# light_switch_hi_volt.net
KiCad netlist of a schematic drawn in EAGLE
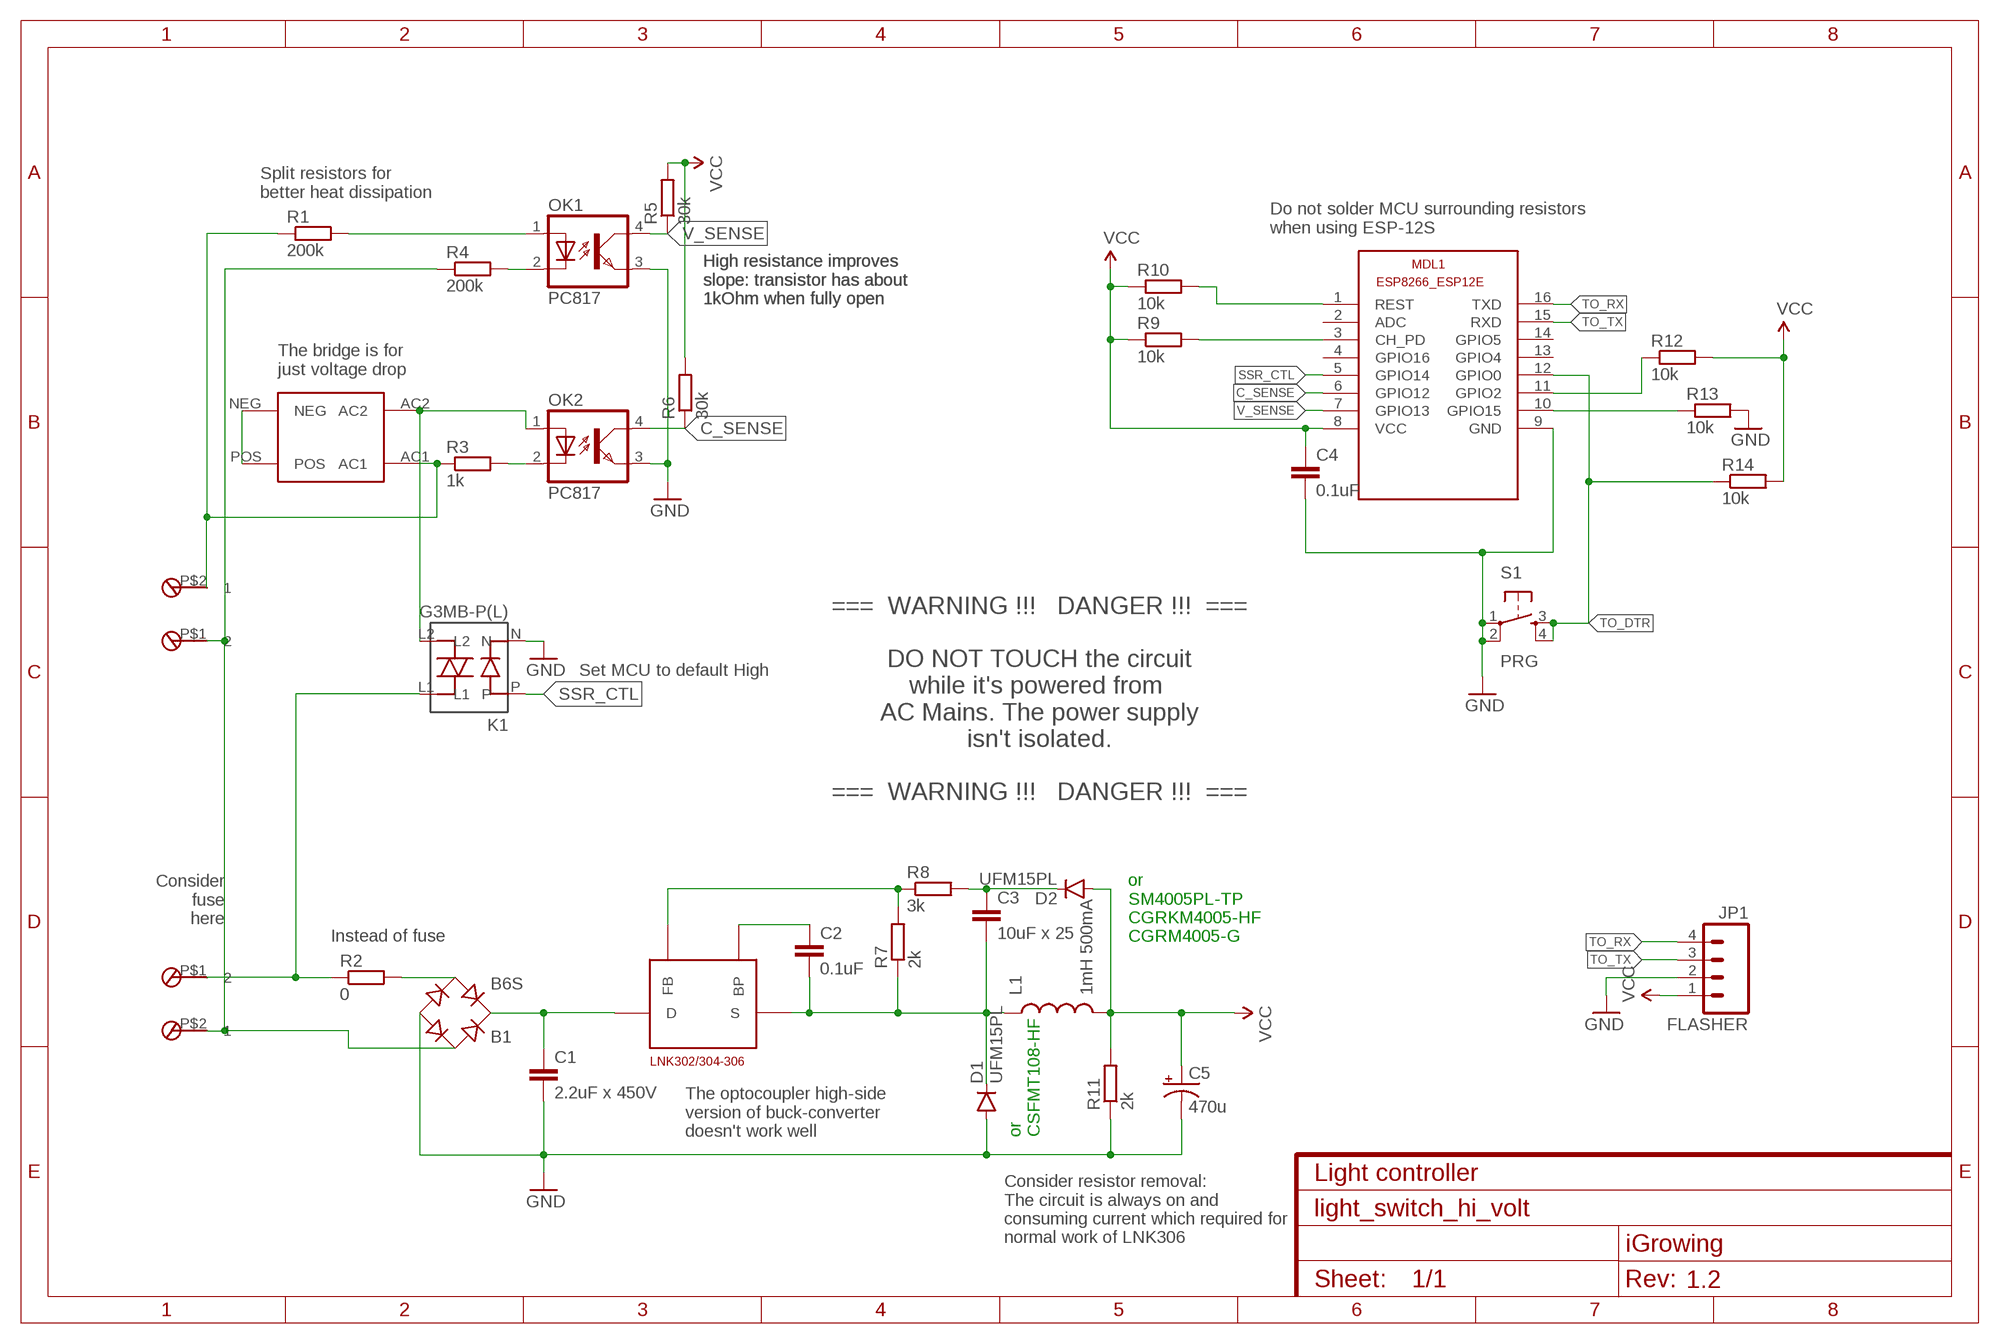
[diagram p0: schematic, sheet 1]

(export (version "E")
  (design (tool "Eeschema 10.0.6"))
  (components
    (comp (ref "B1")
      (value "B6S")
      (footprint "eagle-import:MBS")
      (libsource (lib "eagle-import") (part "BS6"))
    )
    (comp (ref "C1")
      (value "2.2uF x 450V")
      (footprint "eagle-import:C2220K")
      (fields (field (name "MPN") "CKG57NX7T2W225M500JH"))
      (libsource (lib "eagle-import") (part "C-EUC2220K"))
    )
    (comp (ref "C2")
      (value "0.1uF")
      (footprint "eagle-import:0805")
      (fields (field (name "MF") "Taiyo Yuden (U.S.A.), Inc.") (field (name "MPN") "TMK107BJ104KA-T"))
      (libsource (lib "eagle-import") (part "CAP0805"))
    )
    (comp (ref "C3")
      (value "10uF x 25")
      (footprint "eagle-import:0805")
      (fields (field (name "MPN") "GRM219R61E106KA12D"))
      (libsource (lib "eagle-import") (part "SparkFun-Passives_CAP0805"))
    )
    (comp (ref "C4")
      (value "0.1uF")
      (footprint "eagle-import:0805")
      (fields (field (name "MF") "Taiyo Yuden (U.S.A.), Inc.") (field (name "MPN") "TMK107BJ104KA-T"))
      (libsource (lib "eagle-import") (part "CAP0805"))
    )
    (comp (ref "C5")
      (value "470u")
      (footprint "eagle-import:EIA7343")
      (libsource (lib "eagle-import") (part "CAP_POL7343"))
    )
    (comp (ref "D1")
      (value "UFM15PL")
      (footprint "eagle-import:SOD-123")
      (fields (field (name "MPN") "UFM15PL-TP"))
      (libsource (lib "eagle-import") (part "DIODESOD123"))
    )
    (comp (ref "D2")
      (value "UFM15PL")
      (footprint "eagle-import:SOD-123")
      (fields (field (name "MPN") "UFM15PL-TP"))
      (libsource (lib "eagle-import") (part "DIODESOD123"))
    )
    (comp (ref "J1")
      (value "2POS_TERM_BLK_10A_3.5MM")
      (footprint "eagle-import:2POS_TERM_BLK_10A_3.5MM")
      (libsource (lib "eagle-import") (part "2POS_TERM_BLK_10A_3.5MM"))
    )
    (comp (ref "J2")
      (value "2POS_TERM_BLK_10A_3.5MM")
      (footprint "eagle-import:2POS_TERM_BLK_10A_3.5MM")
      (libsource (lib "eagle-import") (part "2POS_TERM_BLK_10A_3.5MM"))
    )
    (comp (ref "JP1")
      (value "FLASHER")
      (footprint "eagle-import:1X04")
      (libsource (lib "eagle-import") (part "M04PTH"))
    )
    (comp (ref "K1")
      (value "G3MB-P(L)")
      (footprint "eagle-import:GB3M_SSR")
      (libsource (lib "eagle-import") (part "G3MB"))
    )
    (comp (ref "L1")
      (value "1mH 500mA")
      (footprint "eagle-import:CDRH125")
      (fields (field (name "MPN") "46105C"))
      (libsource (lib "eagle-import") (part "INDUCTORPWR"))
    )
    (comp (ref "MDL1")
      (value "ESP8266-12EESP8266-ESP12E")
      (footprint "eagle-import:ESP8266-ESP12E")
      (libsource (lib "eagle-import") (part "ESP8266-12EESP8266-ESP12E"))
    )
    (comp (ref "OK1")
      (value "PC817")
      (footprint "eagle-import:SMD4")
      (libsource (lib "eagle-import") (part "LTV816S"))
    )
    (comp (ref "OK2")
      (value "PC817")
      (footprint "eagle-import:SMD4")
      (libsource (lib "eagle-import") (part "LTV816S"))
    )
    (comp (ref "R1")
      (value "200k")
      (footprint "eagle-import:R0805")
      (fields (field (name "MF") "VISHAY/DALE") (field (name "MPN") "CRCW06032K00FKEA"))
      (libsource (lib "eagle-import") (part "resistor_R-EU_R0805"))
    )
    (comp (ref "R2")
      (value "0")
      (footprint "eagle-import:R0603")
      (fields (field (name "MF") "VISHAY/DALE") (field (name "MPN") "CRCW06032K00FKEA"))
      (libsource (lib "eagle-import") (part "resistor_R-EU_R0603"))
    )
    (comp (ref "R3")
      (value "1k")
      (footprint "eagle-import:R0603")
      (fields (field (name "MF") "VISHAY/DALE") (field (name "MPN") "CRCW06032K00FKEA"))
      (libsource (lib "eagle-import") (part "resistor_R-EU_R0603"))
    )
    (comp (ref "R4")
      (value "200k")
      (footprint "eagle-import:R0805")
      (fields (field (name "MF") "VISHAY/DALE") (field (name "MPN") "CRCW06032K00FKEA"))
      (libsource (lib "eagle-import") (part "resistor_R-EU_R0805"))
    )
    (comp (ref "R5")
      (value "30k")
      (footprint "eagle-import:R0603")
      (fields (field (name "MF") "VISHAY/DALE") (field (name "MPN") "CRCW06032K00FKEA"))
      (libsource (lib "eagle-import") (part "resistor_R-EU_R0603"))
    )
    (comp (ref "R6")
      (value "30k")
      (footprint "eagle-import:R0603")
      (fields (field (name "MF") "VISHAY/DALE") (field (name "MPN") "CRCW06032K00FKEA"))
      (libsource (lib "eagle-import") (part "resistor_R-EU_R0603"))
    )
    (comp (ref "R7")
      (value "2k")
      (footprint "eagle-import:R0603")
      (fields (field (name "MF") "VISHAY/DALE") (field (name "MPN") "CRCW06032K00FKEA"))
      (libsource (lib "eagle-import") (part "resistor_R-EU_R0603"))
    )
    (comp (ref "R8")
      (value "3k")
      (footprint "eagle-import:R0603")
      (fields (field (name "MF") "VISHAY/DALE") (field (name "MPN") "CRCW06032K00FKEA"))
      (libsource (lib "eagle-import") (part "resistor_R-EU_R0603"))
    )
    (comp (ref "R9")
      (value "10k")
      (footprint "eagle-import:R0603")
      (libsource (lib "eagle-import") (part "R-EU_R0603"))
    )
    (comp (ref "R10")
      (value "10k")
      (footprint "eagle-import:R0603")
      (libsource (lib "eagle-import") (part "R-EU_R0603"))
    )
    (comp (ref "R11")
      (value "2k")
      (footprint "eagle-import:R0603")
      (fields (field (name "MF") "VISHAY/DALE") (field (name "MPN") "CRCW06032K00FKEA"))
      (libsource (lib "eagle-import") (part "resistor_R-EU_R0603"))
    )
    (comp (ref "R12")
      (value "10k")
      (footprint "eagle-import:R0603")
      (libsource (lib "eagle-import") (part "R-EU_R0603"))
    )
    (comp (ref "R13")
      (value "10k")
      (footprint "eagle-import:R0603")
      (libsource (lib "eagle-import") (part "R-EU_R0603"))
    )
    (comp (ref "R14")
      (value "10k")
      (footprint "eagle-import:R0603")
      (libsource (lib "eagle-import") (part "R-EU_R0603"))
    )
    (comp (ref "S1")
      (value "PRG")
      (footprint "eagle-import:TACTILE-SWITCH-SMD")
      (libsource (lib "eagle-import") (part "TAC_SWITCHSMD"))
    )
    (comp (ref "U1")
      (value "Z4DGP406L-HF")
      (footprint "eagle-import:Z4DGP406L-HF")
      (libsource (lib "eagle-import") (part "Z4DGP406L-HF"))
    )
    (comp (ref "U2")
      (value "LNK306")
      (footprint "eagle-import:SO08")
      (fields (field (name "MPN") "LNK306GN"))
      (libsource (lib "eagle-import") (part "LNK306"))
    )
  )
  (nets
    (net (code "1") (name "C_SENSE") (class "Default")
      (node (ref "MDL1") (pin "6") (pinfunction "GPIO12_6") (pintype "bidirectional"))
      (node (ref "OK2") (pin "4") (pinfunction "COL_4") (pintype "passive"))
      (node (ref "R6") (pin "1") (pinfunction "1_1") (pintype "passive"))
    )
    (net (code "2") (name "GND") (class "Default")
      (node (ref "B1") (pin "-") (pinfunction "-_-") (pintype "passive"))
      (node (ref "C1") (pin "2") (pinfunction "2_2") (pintype "passive"))
      (node (ref "C4") (pin "2") (pinfunction "2_2") (pintype "passive"))
      (node (ref "C5") (pin "C") (pinfunction "-_C") (pintype "passive"))
      (node (ref "D1") (pin "A") (pinfunction "A_A") (pintype "passive"))
      (node (ref "JP1") (pin "2") (pinfunction "2_2") (pintype "passive"))
      (node (ref "K1") (pin "N") (pinfunction "N_N") (pintype "bidirectional"))
      (node (ref "MDL1") (pin "9") (pinfunction "GND_9") (pintype "bidirectional"))
      (node (ref "OK1") (pin "3") (pinfunction "EMIT_3") (pintype "passive"))
      (node (ref "OK2") (pin "3") (pinfunction "EMIT_3") (pintype "passive"))
      (node (ref "R11") (pin "1") (pinfunction "1_1") (pintype "passive"))
      (node (ref "R13") (pin "2") (pinfunction "2_2") (pintype "passive"))
      (node (ref "S1") (pin "1") (pinfunction "1_1") (pintype "passive"))
      (node (ref "S1") (pin "2") (pinfunction "2_2") (pintype "passive"))
    )
    (net (code "3") (name "Net-(B1-PadAC2)") (class "Default")
      (node (ref "B1") (pin "AC2") (pinfunction "AC2_AC2") (pintype "passive"))
      (node (ref "R2") (pin "2") (pinfunction "2_2") (pintype "passive"))
    )
    (net (code "4") (name "Net-(C2-Pad2)") (class "Default")
      (node (ref "C2") (pin "2") (pinfunction "2_2") (pintype "passive"))
      (node (ref "C3") (pin "2") (pinfunction "2_2") (pintype "passive"))
      (node (ref "D1") (pin "C") (pinfunction "C_C") (pintype "passive"))
      (node (ref "L1") (pin "1") (pinfunction "1_1") (pintype "passive"))
      (node (ref "R7") (pin "1") (pinfunction "1_1") (pintype "passive"))
      (node (ref "U2") (pin "5") (pinfunction "S_5") (pintype "bidirectional"))
      (node (ref "U2") (pin "6") (pinfunction "S_6") (pintype "bidirectional"))
      (node (ref "U2") (pin "7") (pinfunction "S_7") (pintype "bidirectional"))
      (node (ref "U2") (pin "8") (pinfunction "S_8") (pintype "bidirectional"))
    )
    (net (code "5") (name "Net-(C3-Pad1)") (class "Default")
      (node (ref "C3") (pin "1") (pinfunction "1_1") (pintype "passive"))
      (node (ref "D2") (pin "C") (pinfunction "C_C") (pintype "passive"))
      (node (ref "R8") (pin "2") (pinfunction "2_2") (pintype "passive"))
    )
    (net (code "6") (name "Net-(J1-1)") (class "Default")
      (node (ref "J1") (pin "P$2") (pinfunction "1_P$2") (pintype "bidirectional"))
      (node (ref "R1") (pin "1") (pinfunction "1_1") (pintype "passive"))
      (node (ref "R3") (pin "1") (pinfunction "1_1") (pintype "passive"))
      (node (ref "U1") (pin "AC1") (pinfunction "AC1_AC1") (pintype "input"))
    )
    (net (code "7") (name "Net-(J1-2)") (class "Default")
      (node (ref "B1") (pin "AC1") (pinfunction "AC1_AC1") (pintype "passive"))
      (node (ref "J1") (pin "P$1") (pinfunction "2_P$1") (pintype "bidirectional"))
      (node (ref "J2") (pin "P$2") (pinfunction "1_P$2") (pintype "bidirectional"))
      (node (ref "R4") (pin "1") (pinfunction "1_1") (pintype "passive"))
    )
    (net (code "8") (name "Net-(J2-2)") (class "Default")
      (node (ref "J2") (pin "P$1") (pinfunction "2_P$1") (pintype "bidirectional"))
      (node (ref "K1") (pin "L1") (pinfunction "L1_L1") (pintype "bidirectional"))
      (node (ref "R2") (pin "1") (pinfunction "1_1") (pintype "passive"))
    )
    (net (code "9") (name "Net-(MDL1-CH_PD)") (class "Default")
      (node (ref "MDL1") (pin "3") (pinfunction "CH_PD_3") (pintype "bidirectional"))
      (node (ref "R9") (pin "2") (pinfunction "2_2") (pintype "passive"))
    )
    (net (code "10") (name "Net-(MDL1-GPIO2)") (class "Default")
      (node (ref "MDL1") (pin "11") (pinfunction "GPIO2_11") (pintype "bidirectional"))
      (node (ref "R12") (pin "1") (pinfunction "1_1") (pintype "passive"))
    )
    (net (code "11") (name "Net-(MDL1-GPIO15)") (class "Default")
      (node (ref "MDL1") (pin "10") (pinfunction "GPIO15_10") (pintype "bidirectional"))
      (node (ref "R13") (pin "1") (pinfunction "1_1") (pintype "passive"))
    )
    (net (code "12") (name "Net-(MDL1-REST)") (class "Default")
      (node (ref "MDL1") (pin "1") (pinfunction "REST_1") (pintype "bidirectional"))
      (node (ref "R10") (pin "2") (pinfunction "2_2") (pintype "passive"))
    )
    (net (code "13") (name "Net-(OK1-A)") (class "Default")
      (node (ref "OK1") (pin "1") (pinfunction "A_1") (pintype "passive"))
      (node (ref "R1") (pin "2") (pinfunction "2_2") (pintype "passive"))
    )
    (net (code "14") (name "Net-(OK1-C)") (class "Default")
      (node (ref "OK1") (pin "2") (pinfunction "C_2") (pintype "passive"))
      (node (ref "R4") (pin "2") (pinfunction "2_2") (pintype "passive"))
    )
    (net (code "15") (name "Net-(OK2-A)") (class "Default")
      (node (ref "K1") (pin "L2") (pinfunction "L2_L2") (pintype "bidirectional"))
      (node (ref "OK2") (pin "1") (pinfunction "A_1") (pintype "passive"))
      (node (ref "U1") (pin "AC2") (pinfunction "AC2_AC2") (pintype "input"))
    )
    (net (code "16") (name "Net-(OK2-C)") (class "Default")
      (node (ref "OK2") (pin "2") (pinfunction "C_2") (pintype "passive"))
      (node (ref "R3") (pin "2") (pinfunction "2_2") (pintype "passive"))
    )
    (net (code "17") (name "Net-(U1-PadNEG)") (class "Default")
      (node (ref "U1") (pin "NEG") (pinfunction "NEG_NEG") (pintype "output"))
      (node (ref "U1") (pin "POS") (pinfunction "POS_POS") (pintype "output"))
    )
    (net (code "18") (name "Net-(U2-BP)") (class "Default")
      (node (ref "C2") (pin "1") (pinfunction "1_1") (pintype "passive"))
      (node (ref "U2") (pin "1") (pinfunction "BP_1") (pintype "bidirectional"))
    )
    (net (code "19") (name "Net-(U2-D)") (class "Default")
      (node (ref "B1") (pin "+") (pinfunction "+_+") (pintype "passive"))
      (node (ref "C1") (pin "1") (pinfunction "1_1") (pintype "passive"))
      (node (ref "U2") (pin "4") (pinfunction "D_4") (pintype "bidirectional"))
    )
    (net (code "20") (name "Net-(U2-FB)") (class "Default")
      (node (ref "R7") (pin "2") (pinfunction "2_2") (pintype "passive"))
      (node (ref "R8") (pin "1") (pinfunction "1_1") (pintype "passive"))
      (node (ref "U2") (pin "2") (pinfunction "FB_2") (pintype "bidirectional"))
    )
    (net (code "21") (name "SSR_CTL") (class "Default")
      (node (ref "K1") (pin "P") (pinfunction "P_P") (pintype "bidirectional"))
      (node (ref "MDL1") (pin "5") (pinfunction "GPIO14_5") (pintype "bidirectional"))
    )
    (net (code "22") (name "TO_DTR") (class "Default")
      (node (ref "MDL1") (pin "12") (pinfunction "GPIO0_12") (pintype "bidirectional"))
      (node (ref "R14") (pin "1") (pinfunction "1_1") (pintype "passive"))
      (node (ref "S1") (pin "3") (pinfunction "3_3") (pintype "passive"))
      (node (ref "S1") (pin "4") (pinfunction "4_4") (pintype "passive"))
    )
    (net (code "23") (name "TO_RX") (class "Default")
      (node (ref "JP1") (pin "4") (pinfunction "4_4") (pintype "passive"))
      (node (ref "MDL1") (pin "16") (pinfunction "TXD_16") (pintype "bidirectional"))
    )
    (net (code "24") (name "TO_TX") (class "Default")
      (node (ref "JP1") (pin "3") (pinfunction "3_3") (pintype "passive"))
      (node (ref "MDL1") (pin "15") (pinfunction "RXD_15") (pintype "bidirectional"))
    )
    (net (code "25") (name "VCC") (class "Default")
      (node (ref "C4") (pin "1") (pinfunction "1_1") (pintype "passive"))
      (node (ref "C5") (pin "A") (pinfunction "+_A") (pintype "passive"))
      (node (ref "D2") (pin "A") (pinfunction "A_A") (pintype "passive"))
      (node (ref "JP1") (pin "1") (pinfunction "1_1") (pintype "passive"))
      (node (ref "L1") (pin "2") (pinfunction "2_2") (pintype "passive"))
      (node (ref "MDL1") (pin "8") (pinfunction "VCC_8") (pintype "bidirectional"))
      (node (ref "R10") (pin "1") (pinfunction "1_1") (pintype "passive"))
      (node (ref "R11") (pin "2") (pinfunction "2_2") (pintype "passive"))
      (node (ref "R12") (pin "2") (pinfunction "2_2") (pintype "passive"))
      (node (ref "R14") (pin "2") (pinfunction "2_2") (pintype "passive"))
      (node (ref "R5") (pin "2") (pinfunction "2_2") (pintype "passive"))
      (node (ref "R6") (pin "2") (pinfunction "2_2") (pintype "passive"))
      (node (ref "R9") (pin "1") (pinfunction "1_1") (pintype "passive"))
    )
    (net (code "26") (name "V_SENSE") (class "Default")
      (node (ref "MDL1") (pin "7") (pinfunction "GPIO13_7") (pintype "bidirectional"))
      (node (ref "OK1") (pin "4") (pinfunction "COL_4") (pintype "passive"))
      (node (ref "R5") (pin "1") (pinfunction "1_1") (pintype "passive"))
    )
    (net (code "27") (name "unconnected-(MDL1-ADC-Pad2)") (class "Default")
      (node (ref "MDL1") (pin "2") (pinfunction "ADC_2") (pintype "bidirectional"))
    )
    (net (code "28") (name "unconnected-(MDL1-GPIO4-Pad13)") (class "Default")
      (node (ref "MDL1") (pin "13") (pinfunction "GPIO4_13") (pintype "bidirectional"))
    )
    (net (code "29") (name "unconnected-(MDL1-GPIO5-Pad14)") (class "Default")
      (node (ref "MDL1") (pin "14") (pinfunction "GPIO5_14") (pintype "bidirectional"))
    )
    (net (code "30") (name "unconnected-(MDL1-GPIO16-Pad4)") (class "Default")
      (node (ref "MDL1") (pin "4") (pinfunction "GPIO16_4") (pintype "bidirectional"))
    )
  )
)
